# HydrophoneGroup3FilterAndAmpCircuit.net
KiCad netlist of a schematic drawn in Altium Designer
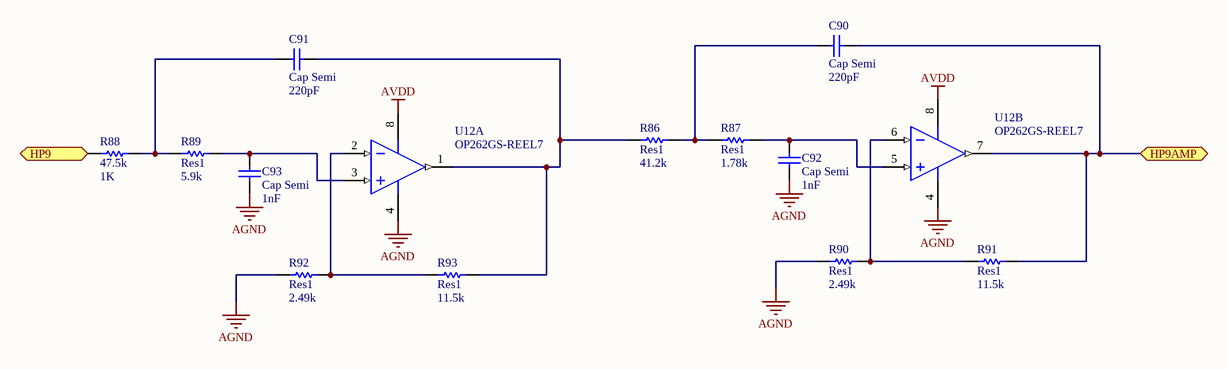
[diagram p0: HydrophoneGroup3FilterAndAmpCircuit.SchDoc]

(export (version "E")
  (design (tool "Eeschema 10.0.6"))
  (components
    (comp (ref "C90")
      (value "Cap Semi")
      (footprint "0402")
      (description "Capacitor (Semiconductor SIM Model)")
      (fields (field (name "ALTIUM_VALUE") "220pF") (field (name "PUBLISHER") "Altium Limited"))
      (libsource (lib "Miscellaneous Devices") (part "Cap Semi"))
    )
    (comp (ref "C91")
      (value "Cap Semi")
      (footprint "0402")
      (description "Capacitor (Semiconductor SIM Model)")
      (fields (field (name "ALTIUM_VALUE") "220pF") (field (name "PUBLISHER") "Altium Limited"))
      (libsource (lib "Miscellaneous Devices") (part "Cap Semi"))
    )
    (comp (ref "C92")
      (value "Cap Semi")
      (footprint "0402")
      (description "Capacitor (Semiconductor SIM Model)")
      (fields (field (name "ALTIUM_VALUE") "1nF") (field (name "PUBLISHER") "Altium Limited"))
      (libsource (lib "Miscellaneous Devices") (part "Cap Semi"))
    )
    (comp (ref "C93")
      (value "Cap Semi")
      (footprint "0402")
      (description "Capacitor (Semiconductor SIM Model)")
      (fields (field (name "ALTIUM_VALUE") "1nF") (field (name "PUBLISHER") "Altium Limited"))
      (libsource (lib "Miscellaneous Devices") (part "Cap Semi"))
    )
    (comp (ref "R86")
      (value "Res1")
      (footprint "AXIAL-0.3")
      (description "Resistor")
      (fields (field (name "ALTIUM_VALUE") "41.2k") (field (name "PUBLISHER") "Altium Limited"))
      (libsource (lib "Miscellaneous Devices") (part "Res1"))
    )
    (comp (ref "R87")
      (value "Res1")
      (footprint "AXIAL-0.3")
      (description "Resistor")
      (fields (field (name "ALTIUM_VALUE") "1.78k") (field (name "PUBLISHER") "Altium Limited"))
      (libsource (lib "Miscellaneous Devices") (part "Res1"))
    )
    (comp (ref "R88")
      (value "47.5k")
      (footprint "AXIAL-0.3")
      (description "Resistor")
      (fields (field (name "ALTIUM_VALUE") "1K") (field (name "PUBLISHER") "Altium Limited"))
      (libsource (lib "Miscellaneous Devices") (part "Res1"))
    )
    (comp (ref "R89")
      (value "Res1")
      (footprint "AXIAL-0.3")
      (description "Resistor")
      (fields (field (name "ALTIUM_VALUE") "5.9k") (field (name "PUBLISHER") "Altium Limited"))
      (libsource (lib "Miscellaneous Devices") (part "Res1"))
    )
    (comp (ref "R90")
      (value "Res1")
      (footprint "AXIAL-0.3")
      (description "Resistor")
      (fields (field (name "ALTIUM_VALUE") "2.49k") (field (name "PUBLISHER") "Altium Limited"))
      (libsource (lib "Miscellaneous Devices") (part "Res1"))
    )
    (comp (ref "R91")
      (value "Res1")
      (footprint "AXIAL-0.3")
      (description "Resistor")
      (fields (field (name "ALTIUM_VALUE") "11.5k") (field (name "PUBLISHER") "Altium Limited"))
      (libsource (lib "Miscellaneous Devices") (part "Res1"))
    )
    (comp (ref "R92")
      (value "Res1")
      (footprint "AXIAL-0.3")
      (description "Resistor")
      (fields (field (name "ALTIUM_VALUE") "2.49k") (field (name "PUBLISHER") "Altium Limited"))
      (libsource (lib "Miscellaneous Devices") (part "Res1"))
    )
    (comp (ref "R93")
      (value "Res1")
      (footprint "AXIAL-0.3")
      (description "Resistor")
      (fields (field (name "ALTIUM_VALUE") "11.5k") (field (name "PUBLISHER") "Altium Limited"))
      (libsource (lib "Miscellaneous Devices") (part "Res1"))
    )
    (comp (ref "U12")
      (value "OP262GS-REEL7")
      (footprint "ADI-R-8_L")
      (fields (field (name "GENERIC PART NUMBER") "OP262") (field (name "MANUFACTURER") "Analog Devices"))
      (libsource (lib "Altium Content Vault") (part "ADI-OP29X-R-8"))
    )
  )
  (nets
    (net (code "1") (name "/HP9") (class "Default")
      (node (ref "R88") (pin "1") (pinfunction "1_1") (pintype "passive"))
    )
    (net (code "2") (name "/HP9AMP") (class "Default")
      (node (ref "C90") (pin "2") (pinfunction "2_2") (pintype "passive"))
      (node (ref "R91") (pin "2") (pinfunction "2_2") (pintype "passive"))
      (node (ref "U12") (pin "7") (pinfunction "OUT_B_7") (pintype "output"))
    )
    (net (code "3") (name "AGND") (class "Default")
      (node (ref "C92") (pin "1") (pinfunction "1_1") (pintype "passive"))
      (node (ref "C93") (pin "1") (pinfunction "1_1") (pintype "passive"))
      (node (ref "R90") (pin "1") (pinfunction "1_1") (pintype "passive"))
      (node (ref "R92") (pin "1") (pinfunction "1_1") (pintype "passive"))
      (node (ref "U12") (pin "4") (pinfunction "-V_4") (pintype "power_in"))
    )
    (net (code "4") (name "AVDD") (class "Default")
      (node (ref "U12") (pin "8") (pinfunction "+V_8") (pintype "power_in"))
    )
    (net (code "5") (name "Net-(C90-Pad1)") (class "Default")
      (node (ref "C90") (pin "1") (pinfunction "1_1") (pintype "passive"))
      (node (ref "R86") (pin "2") (pinfunction "2_2") (pintype "passive"))
      (node (ref "R87") (pin "1") (pinfunction "1_1") (pintype "passive"))
    )
    (net (code "6") (name "Net-(C91-Pad1)") (class "Default")
      (node (ref "C91") (pin "1") (pinfunction "1_1") (pintype "passive"))
      (node (ref "R88") (pin "2") (pinfunction "2_2") (pintype "passive"))
      (node (ref "R89") (pin "1") (pinfunction "1_1") (pintype "passive"))
    )
    (net (code "7") (name "Net-(U12A-+IN_A)") (class "Default")
      (node (ref "C93") (pin "2") (pinfunction "2_2") (pintype "passive"))
      (node (ref "R89") (pin "2") (pinfunction "2_2") (pintype "passive"))
      (node (ref "U12") (pin "3") (pinfunction "+IN_A_3") (pintype "input"))
    )
    (net (code "8") (name "Net-(U12A--IN_A)") (class "Default")
      (node (ref "R92") (pin "2") (pinfunction "2_2") (pintype "passive"))
      (node (ref "R93") (pin "1") (pinfunction "1_1") (pintype "passive"))
      (node (ref "U12") (pin "2") (pinfunction "-IN_A_2") (pintype "input"))
    )
    (net (code "9") (name "Net-(U12A-OUT_A)") (class "Default")
      (node (ref "C91") (pin "2") (pinfunction "2_2") (pintype "passive"))
      (node (ref "R86") (pin "1") (pinfunction "1_1") (pintype "passive"))
      (node (ref "R93") (pin "2") (pinfunction "2_2") (pintype "passive"))
      (node (ref "U12") (pin "1") (pinfunction "OUT_A_1") (pintype "output"))
    )
    (net (code "10") (name "Net-(U12B-+IN_B)") (class "Default")
      (node (ref "C92") (pin "2") (pinfunction "2_2") (pintype "passive"))
      (node (ref "R87") (pin "2") (pinfunction "2_2") (pintype "passive"))
      (node (ref "U12") (pin "5") (pinfunction "+IN_B_5") (pintype "input"))
    )
    (net (code "11") (name "Net-(U12B--IN_B)") (class "Default")
      (node (ref "R90") (pin "2") (pinfunction "2_2") (pintype "passive"))
      (node (ref "R91") (pin "1") (pinfunction "1_1") (pintype "passive"))
      (node (ref "U12") (pin "6") (pinfunction "-IN_B_6") (pintype "input"))
    )
  )
)
